# GyroAccelHeaders.net
KiCad netlist of a schematic drawn in Altium Designer
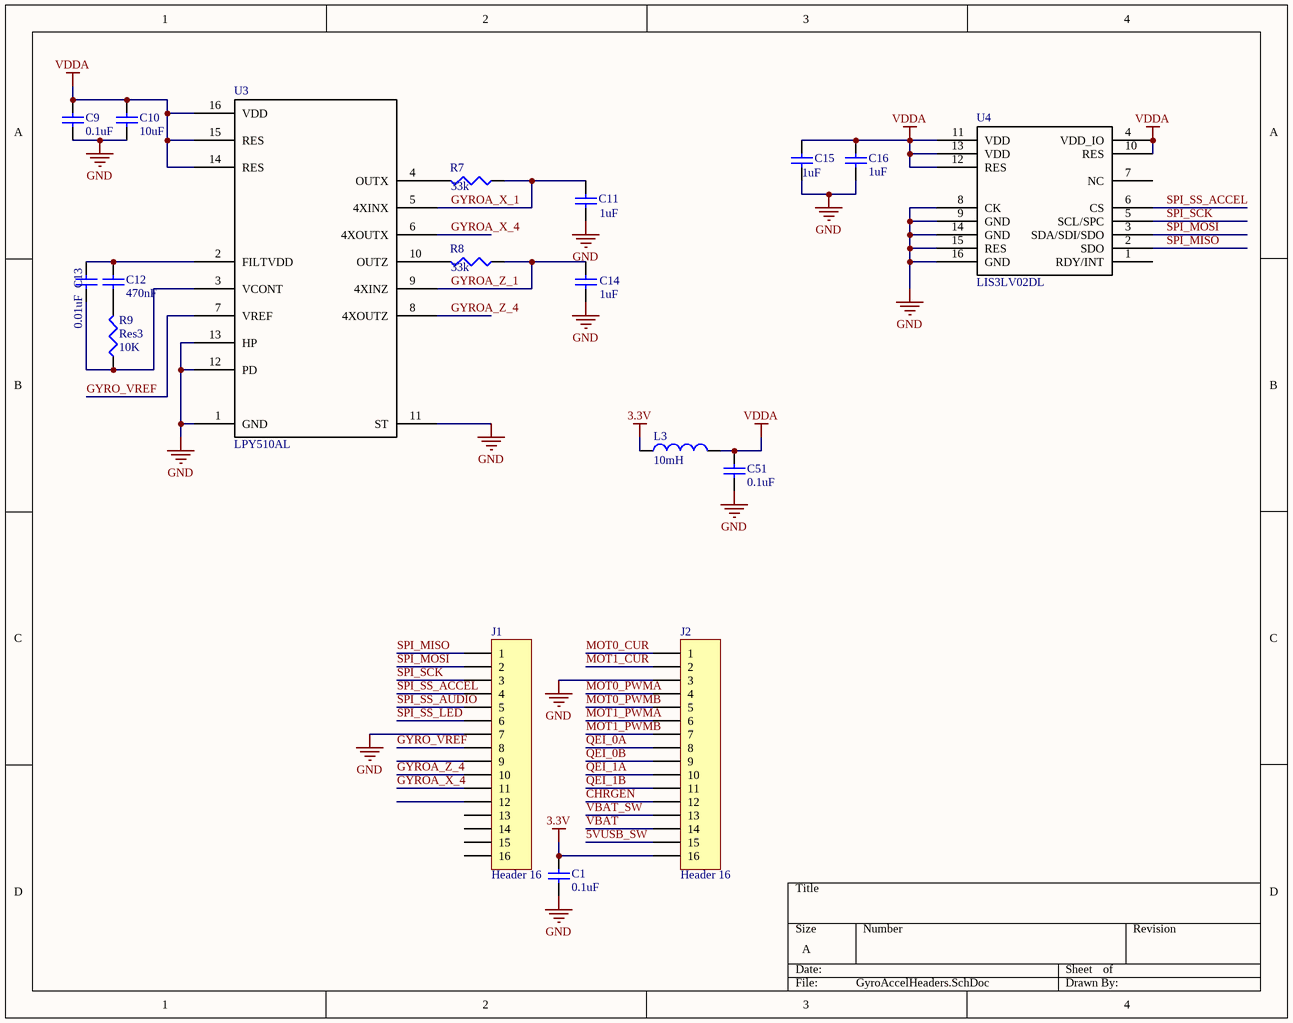
[diagram p0: GyroAccelHeaders.SchDoc]

(export (version "E")
  (design (tool "Eeschema 10.0.6"))
  (components
    (comp (ref "C1")
      (value "0.1uF")
      (footprint "CAPC3216L")
      (description "Capacitor (Semiconductor SIM Model)")
      (fields (field (name "Comment") "Cap Semi") (field (name "PUBLISHER") "Altium Limited"))
      (libsource (lib "Miscellaneous Devices") (part "Cap Semi"))
    )
    (comp (ref "C9")
      (value "0.1uF")
      (footprint "CAPC1005L")
      (description "Capacitor (Semiconductor SIM Model)")
      (fields (field (name "Comment") "Cap Semi") (field (name "PUBLISHER") "Altium Limited"))
      (libsource (lib "Miscellaneous Devices") (part "Cap Semi"))
    )
    (comp (ref "C10")
      (value "10uF")
      (footprint "CAPC1608L")
      (description "Capacitor (Semiconductor SIM Model)")
      (fields (field (name "Comment") "Cap Semi") (field (name "PUBLISHER") "Altium Limited"))
      (libsource (lib "Miscellaneous Devices") (part "Cap Semi"))
    )
    (comp (ref "C11")
      (value "1uF")
      (footprint "CAPC1608L")
      (description "Capacitor (Semiconductor SIM Model)")
      (fields (field (name "Comment") "Cap Semi") (field (name "PUBLISHER") "Altium Limited"))
      (libsource (lib "Miscellaneous Devices") (part "Cap Semi"))
    )
    (comp (ref "C12")
      (value "470nF")
      (footprint "CAPC1005L")
      (description "Capacitor (Semiconductor SIM Model)")
      (fields (field (name "Comment") "Cap Semi") (field (name "PUBLISHER") "Altium Limited"))
      (libsource (lib "Miscellaneous Devices") (part "Cap Semi"))
    )
    (comp (ref "C13")
      (value "0.01uF")
      (footprint "CAPC1005L")
      (description "Capacitor (Semiconductor SIM Model)")
      (fields (field (name "Comment") "Cap Semi") (field (name "PUBLISHER") "Altium Limited"))
      (libsource (lib "Miscellaneous Devices") (part "Cap Semi"))
    )
    (comp (ref "C14")
      (value "1uF")
      (footprint "CAPC1608L")
      (description "Capacitor (Semiconductor SIM Model)")
      (fields (field (name "Comment") "Cap Semi") (field (name "PUBLISHER") "Altium Limited"))
      (libsource (lib "Miscellaneous Devices") (part "Cap Semi"))
    )
    (comp (ref "C15")
      (value "1uF")
      (footprint "CAPC1608L")
      (description "Capacitor (Semiconductor SIM Model)")
      (fields (field (name "Comment") "Cap Semi") (field (name "PUBLISHER") "Altium Limited"))
      (libsource (lib "Miscellaneous Devices") (part "Cap Semi"))
    )
    (comp (ref "C16")
      (value "1uF")
      (footprint "CAPC1608L")
      (description "Capacitor (Semiconductor SIM Model)")
      (fields (field (name "Comment") "Cap Semi") (field (name "PUBLISHER") "Altium Limited"))
      (libsource (lib "Miscellaneous Devices") (part "Cap Semi"))
    )
    (comp (ref "C51")
      (value "0.1uF")
      (footprint "CAPC1005L")
      (description "Capacitor (Semiconductor SIM Model)")
      (fields (field (name "Comment") "Cap Semi") (field (name "PUBLISHER") "Altium Limited"))
      (libsource (lib "Miscellaneous Devices") (part "Cap Semi"))
    )
    (comp (ref "J1")
      (value "Header 16")
      (footprint "HDR1X16")
      (description "Header, 16-Pin")
      (fields (field (name "PUBLISHER") "Altium Limited"))
      (libsource (lib "Miscellaneous Connectors") (part "Header 16"))
    )
    (comp (ref "J2")
      (value "Header 16")
      (footprint "HDR1X16")
      (description "Header, 16-Pin")
      (fields (field (name "PUBLISHER") "Altium Limited"))
      (libsource (lib "Miscellaneous Connectors") (part "Header 16"))
    )
    (comp (ref "L3")
      (value "10mH")
      (footprint "INDC2012L")
      (description "Inductor")
      (fields (field (name "PUBLISHER") "Altium Limited"))
      (libsource (lib "Miscellaneous Devices") (part "Inductor"))
    )
    (comp (ref "R7")
      (value "33k")
      (footprint "RESC1608L")
      (description "Resistor")
      (fields (field (name "Comment") "Res3") (field (name "PUBLISHER") "Altium Limited"))
      (libsource (lib "Miscellaneous Devices") (part "Res3"))
    )
    (comp (ref "R8")
      (value "33k")
      (footprint "RESC1608L")
      (description "Resistor")
      (fields (field (name "Comment") "Res3") (field (name "PUBLISHER") "Altium Limited"))
      (libsource (lib "Miscellaneous Devices") (part "Res3"))
    )
    (comp (ref "R9")
      (value "Res3")
      (footprint "RESC1608L")
      (description "Resistor")
      (fields (field (name "ALTIUM_VALUE") "10K") (field (name "PUBLISHER") "Altium Limited"))
      (libsource (lib "Miscellaneous Devices") (part "Res3"))
    )
    (comp (ref "U3") (value "LPY510AL") (footprint "LGA16") (libsource (lib "mrone") (part "LPY510AL")))
    (comp (ref "U4")
      (value "LIS3LV02DL")
      (footprint "LGA16 (4.4x7.5x1 mm)")
      (libsource (lib "mrone") (part "LIS3LV02DL"))
    )
  )
  (nets
    (net (code "1") (name "/5VUSB_SW") (class "Default")
      (node (ref "J2") (pin "15") (pinfunction "15_15") (pintype "passive"))
    )
    (net (code "2") (name "/CHRGEN") (class "Default")
      (node (ref "J2") (pin "12") (pinfunction "12_12") (pintype "passive"))
    )
    (net (code "3") (name "/GYROA_X_1") (class "Default")
      (node (ref "C11") (pin "2") (pinfunction "2_2") (pintype "passive"))
      (node (ref "R7") (pin "1") (pinfunction "1_1") (pintype "passive"))
      (node (ref "U3") (pin "5") (pinfunction "4XINX_5") (pintype "passive"))
    )
    (net (code "4") (name "/GYROA_X_4") (class "Default")
      (node (ref "J1") (pin "11") (pinfunction "11_11") (pintype "passive"))
      (node (ref "U3") (pin "6") (pinfunction "4XOUTX_6") (pintype "passive"))
    )
    (net (code "5") (name "/GYROA_Z_1") (class "Default")
      (node (ref "C14") (pin "2") (pinfunction "2_2") (pintype "passive"))
      (node (ref "R8") (pin "1") (pinfunction "1_1") (pintype "passive"))
      (node (ref "U3") (pin "9") (pinfunction "4XINZ_9") (pintype "passive"))
    )
    (net (code "6") (name "/GYROA_Z_4") (class "Default")
      (node (ref "J1") (pin "10") (pinfunction "10_10") (pintype "passive"))
      (node (ref "U3") (pin "8") (pinfunction "4XOUTZ_8") (pintype "passive"))
    )
    (net (code "7") (name "/GYRO_VREF") (class "Default")
      (node (ref "J1") (pin "8") (pinfunction "8_8") (pintype "passive"))
      (node (ref "U3") (pin "7") (pinfunction "VREF_7") (pintype "passive"))
    )
    (net (code "8") (name "/MOT0_CUR") (class "Default")
      (node (ref "J2") (pin "1") (pinfunction "1_1") (pintype "passive"))
    )
    (net (code "9") (name "/MOT0_PWMA") (class "Default")
      (node (ref "J2") (pin "4") (pinfunction "4_4") (pintype "passive"))
    )
    (net (code "10") (name "/MOT0_PWMB") (class "Default")
      (node (ref "J2") (pin "5") (pinfunction "5_5") (pintype "passive"))
    )
    (net (code "11") (name "/MOT1_CUR") (class "Default")
      (node (ref "J2") (pin "2") (pinfunction "2_2") (pintype "passive"))
    )
    (net (code "12") (name "/MOT1_PWMA") (class "Default")
      (node (ref "J2") (pin "6") (pinfunction "6_6") (pintype "passive"))
    )
    (net (code "13") (name "/MOT1_PWMB") (class "Default")
      (node (ref "J2") (pin "7") (pinfunction "7_7") (pintype "passive"))
    )
    (net (code "14") (name "/QEI_0A") (class "Default")
      (node (ref "J2") (pin "8") (pinfunction "8_8") (pintype "passive"))
    )
    (net (code "15") (name "/QEI_0B") (class "Default")
      (node (ref "J2") (pin "9") (pinfunction "9_9") (pintype "passive"))
    )
    (net (code "16") (name "/QEI_1A") (class "Default")
      (node (ref "J2") (pin "10") (pinfunction "10_10") (pintype "passive"))
    )
    (net (code "17") (name "/QEI_1B") (class "Default")
      (node (ref "J2") (pin "11") (pinfunction "11_11") (pintype "passive"))
    )
    (net (code "18") (name "/SPI_MISO") (class "Default")
      (node (ref "J1") (pin "1") (pinfunction "1_1") (pintype "passive"))
      (node (ref "U4") (pin "2") (pinfunction "SDO_2") (pintype "passive"))
    )
    (net (code "19") (name "/SPI_MOSI") (class "Default")
      (node (ref "J1") (pin "2") (pinfunction "2_2") (pintype "passive"))
      (node (ref "U4") (pin "3") (pinfunction "SDA/SDI/SDO_3") (pintype "passive"))
    )
    (net (code "20") (name "/SPI_SCK") (class "Default")
      (node (ref "J1") (pin "3") (pinfunction "3_3") (pintype "passive"))
      (node (ref "U4") (pin "5") (pinfunction "SCL/SPC_5") (pintype "passive"))
    )
    (net (code "21") (name "/SPI_SS_ACCEL") (class "Default")
      (node (ref "J1") (pin "4") (pinfunction "4_4") (pintype "passive"))
      (node (ref "U4") (pin "6") (pinfunction "CS_6") (pintype "passive"))
    )
    (net (code "22") (name "/SPI_SS_AUDIO") (class "Default")
      (node (ref "J1") (pin "5") (pinfunction "5_5") (pintype "passive"))
    )
    (net (code "23") (name "/SPI_SS_LED") (class "Default")
      (node (ref "J1") (pin "6") (pinfunction "6_6") (pintype "passive"))
    )
    (net (code "24") (name "/VBAT") (class "Default")
      (node (ref "J2") (pin "14") (pinfunction "14_14") (pintype "passive"))
    )
    (net (code "25") (name "/VBAT_SW") (class "Default")
      (node (ref "J2") (pin "13") (pinfunction "13_13") (pintype "passive"))
    )
    (net (code "26") (name "3.3V") (class "Default")
      (node (ref "C1") (pin "2") (pinfunction "2_2") (pintype "passive"))
      (node (ref "J2") (pin "16") (pinfunction "16_16") (pintype "passive"))
      (node (ref "L3") (pin "2") (pinfunction "2_2") (pintype "passive"))
    )
    (net (code "27") (name "GND") (class "Default")
      (node (ref "C1") (pin "1") (pinfunction "1_1") (pintype "passive"))
      (node (ref "C10") (pin "1") (pinfunction "1_1") (pintype "passive"))
      (node (ref "C11") (pin "1") (pinfunction "1_1") (pintype "passive"))
      (node (ref "C14") (pin "1") (pinfunction "1_1") (pintype "passive"))
      (node (ref "C15") (pin "1") (pinfunction "1_1") (pintype "passive"))
      (node (ref "C16") (pin "1") (pinfunction "1_1") (pintype "passive"))
      (node (ref "C51") (pin "1") (pinfunction "1_1") (pintype "passive"))
      (node (ref "C9") (pin "1") (pinfunction "1_1") (pintype "passive"))
      (node (ref "J1") (pin "7") (pinfunction "7_7") (pintype "passive"))
      (node (ref "J2") (pin "3") (pinfunction "3_3") (pintype "passive"))
      (node (ref "U3") (pin "1") (pinfunction "GND_1") (pintype "passive"))
      (node (ref "U3") (pin "11") (pinfunction "ST_11") (pintype "passive"))
      (node (ref "U3") (pin "12") (pinfunction "PD_12") (pintype "passive"))
      (node (ref "U3") (pin "13") (pinfunction "HP_13") (pintype "passive"))
      (node (ref "U4") (pin "14") (pinfunction "GND_14") (pintype "passive"))
      (node (ref "U4") (pin "15") (pinfunction "RES_15") (pintype "passive"))
      (node (ref "U4") (pin "16") (pinfunction "GND_16") (pintype "passive"))
      (node (ref "U4") (pin "8") (pinfunction "CK_8") (pintype "passive"))
      (node (ref "U4") (pin "9") (pinfunction "GND_9") (pintype "passive"))
    )
    (net (code "28") (name "Net-(C12-Pad1)") (class "Default")
      (node (ref "C12") (pin "1") (pinfunction "1_1") (pintype "passive"))
      (node (ref "R9") (pin "2") (pinfunction "2_2") (pintype "passive"))
    )
    (net (code "29") (name "Net-(U3-FILTVDD)") (class "Default")
      (node (ref "C12") (pin "2") (pinfunction "2_2") (pintype "passive"))
      (node (ref "C13") (pin "2") (pinfunction "2_2") (pintype "passive"))
      (node (ref "U3") (pin "2") (pinfunction "FILTVDD_2") (pintype "passive"))
    )
    (net (code "30") (name "Net-(U3-OUTX)") (class "Default")
      (node (ref "R7") (pin "2") (pinfunction "2_2") (pintype "passive"))
      (node (ref "U3") (pin "4") (pinfunction "OUTX_4") (pintype "passive"))
    )
    (net (code "31") (name "Net-(U3-OUTZ)") (class "Default")
      (node (ref "R8") (pin "2") (pinfunction "2_2") (pintype "passive"))
      (node (ref "U3") (pin "10") (pinfunction "OUTZ_10") (pintype "passive"))
    )
    (net (code "32") (name "Net-(U3-VCONT)") (class "Default")
      (node (ref "C13") (pin "1") (pinfunction "1_1") (pintype "passive"))
      (node (ref "R9") (pin "1") (pinfunction "1_1") (pintype "passive"))
      (node (ref "U3") (pin "3") (pinfunction "VCONT_3") (pintype "passive"))
    )
    (net (code "33") (name "VDDA") (class "Default")
      (node (ref "C10") (pin "2") (pinfunction "2_2") (pintype "passive"))
      (node (ref "C15") (pin "2") (pinfunction "2_2") (pintype "passive"))
      (node (ref "C16") (pin "2") (pinfunction "2_2") (pintype "passive"))
      (node (ref "C51") (pin "2") (pinfunction "2_2") (pintype "passive"))
      (node (ref "C9") (pin "2") (pinfunction "2_2") (pintype "passive"))
      (node (ref "L3") (pin "1") (pinfunction "1_1") (pintype "passive"))
      (node (ref "U3") (pin "14") (pinfunction "RES_14") (pintype "passive"))
      (node (ref "U3") (pin "15") (pinfunction "RES_15") (pintype "passive"))
      (node (ref "U3") (pin "16") (pinfunction "VDD_16") (pintype "passive"))
      (node (ref "U4") (pin "10") (pinfunction "RES_10") (pintype "passive"))
      (node (ref "U4") (pin "11") (pinfunction "VDD_11") (pintype "passive"))
      (node (ref "U4") (pin "12") (pinfunction "RES_12") (pintype "passive"))
      (node (ref "U4") (pin "13") (pinfunction "VDD_13") (pintype "passive"))
      (node (ref "U4") (pin "4") (pinfunction "VDD_IO_4") (pintype "passive"))
    )
    (net (code "34") (name "unconnected-(J1-Pad9)") (class "Default")
      (node (ref "J1") (pin "9") (pinfunction "9_9") (pintype "passive"))
    )
    (net (code "35") (name "unconnected-(J1-Pad12)") (class "Default")
      (node (ref "J1") (pin "12") (pinfunction "12_12") (pintype "passive"))
    )
    (net (code "36") (name "unconnected-(J1-Pad13)") (class "Default")
      (node (ref "J1") (pin "13") (pinfunction "13_13") (pintype "passive"))
    )
    (net (code "37") (name "unconnected-(J1-Pad14)") (class "Default")
      (node (ref "J1") (pin "14") (pinfunction "14_14") (pintype "passive"))
    )
    (net (code "38") (name "unconnected-(J1-Pad15)") (class "Default")
      (node (ref "J1") (pin "15") (pinfunction "15_15") (pintype "passive"))
    )
    (net (code "39") (name "unconnected-(J1-Pad16)") (class "Default")
      (node (ref "J1") (pin "16") (pinfunction "16_16") (pintype "passive"))
    )
    (net (code "40") (name "unconnected-(U4-NC-Pad7)") (class "Default")
      (node (ref "U4") (pin "7") (pinfunction "NC_7") (pintype "passive"))
    )
    (net (code "41") (name "unconnected-(U4-RDY{slash}INT-Pad1)") (class "Default")
      (node (ref "U4") (pin "1") (pinfunction "RDY/INT_1") (pintype "passive"))
    )
  )
)
